# esp-mqtt-doorbell-receiver.net
KiCad netlist of a schematic drawn in EAGLE
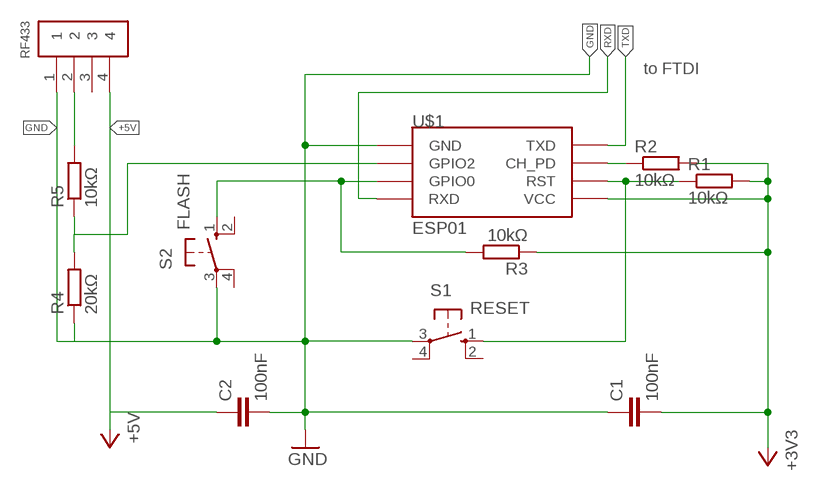
[diagram p0: schematic, sheet 1]

(export (version "E")
  (design (tool "Eeschema 10.0.6"))
  (components
    (comp (ref "C1")
      (value "100nF")
      (footprint "eagle-import:C025-025X050")
      (libsource (lib "eagle-import") (part "C-EU025-025X050"))
    )
    (comp (ref "C2")
      (value "100nF")
      (footprint "eagle-import:C025-025X050")
      (libsource (lib "eagle-import") (part "C-EU025-025X050"))
    )
    (comp (ref "R1")
      (value "10kΩ")
      (footprint "eagle-import:0204_7")
      (libsource (lib "eagle-import") (part "R-EU_0204/7"))
    )
    (comp (ref "R2")
      (value "10kΩ")
      (footprint "eagle-import:0204_7")
      (libsource (lib "eagle-import") (part "R-EU_0204/7"))
    )
    (comp (ref "R3")
      (value "10kΩ")
      (footprint "eagle-import:0204_7")
      (libsource (lib "eagle-import") (part "R-EU_0204/7"))
    )
    (comp (ref "R4")
      (value "20kΩ")
      (footprint "eagle-import:0204_7")
      (libsource (lib "eagle-import") (part "R-EU_0204/7"))
    )
    (comp (ref "R5")
      (value "10kΩ")
      (footprint "eagle-import:0204_7")
      (libsource (lib "eagle-import") (part "R-EU_0204/7"))
    )
    (comp (ref "RF433")
      (value "1X4-BIG")
      (footprint "eagle-import:1X04-BIG")
      (libsource (lib "eagle-import") (part "1X4-BIG"))
    )
    (comp (ref "S1")
      (value "RESET")
      (footprint "eagle-import:B3F-10XX")
      (fields (field (name "MPN") "B3F-1000"))
      (libsource (lib "eagle-import") (part "10-XX"))
    )
    (comp (ref "S2")
      (value "FLASH")
      (footprint "eagle-import:B3F-10XX")
      (fields (field (name "MPN") "B3F-1000"))
      (libsource (lib "eagle-import") (part "10-XX"))
    )
    (comp (ref "U$1")
      (value "ESP01")
      (footprint "eagle-import:ESP01")
      (libsource (lib "eagle-import") (part "ESP01"))
    )
  )
  (nets
    (net (code "1") (name "+3V3") (class "Default")
      (node (ref "C1") (pin "2") (pinfunction "2_2") (pintype "passive"))
      (node (ref "R1") (pin "2") (pinfunction "2_2") (pintype "passive"))
      (node (ref "R2") (pin "2") (pinfunction "2_2") (pintype "passive"))
      (node (ref "R3") (pin "1") (pinfunction "1_1") (pintype "passive"))
      (node (ref "U$1") (pin "VCC") (pinfunction "VCC_VCC") (pintype "bidirectional"))
    )
    (net (code "2") (name "+5V") (class "Default")
      (node (ref "C2") (pin "1") (pinfunction "1_1") (pintype "passive"))
      (node (ref "RF433") (pin "4") (pinfunction "4_4") (pintype "bidirectional"))
    )
    (net (code "3") (name "GND") (class "Default")
      (node (ref "C1") (pin "1") (pinfunction "1_1") (pintype "passive"))
      (node (ref "C2") (pin "2") (pinfunction "2_2") (pintype "passive"))
      (node (ref "R4") (pin "1") (pinfunction "1_1") (pintype "passive"))
      (node (ref "RF433") (pin "1") (pinfunction "1_1") (pintype "bidirectional"))
      (node (ref "S1") (pin "3") (pinfunction "P_3") (pintype "passive"))
      (node (ref "S2") (pin "3") (pinfunction "P_3") (pintype "passive"))
      (node (ref "U$1") (pin "GND") (pinfunction "GND_GND") (pintype "bidirectional"))
    )
    (net (code "4") (name "Net-(R2-Pad1)") (class "Default")
      (node (ref "R2") (pin "1") (pinfunction "1_1") (pintype "passive"))
      (node (ref "U$1") (pin "CH_PD") (pinfunction "CH_PD_CH_PD") (pintype "bidirectional"))
    )
    (net (code "5") (name "Net-(R4-Pad2)") (class "Default")
      (node (ref "R4") (pin "2") (pinfunction "2_2") (pintype "passive"))
      (node (ref "R5") (pin "1") (pinfunction "1_1") (pintype "passive"))
      (node (ref "U$1") (pin "GPIO2") (pinfunction "GPIO2_GPIO2") (pintype "bidirectional"))
    )
    (net (code "6") (name "Net-(R5-Pad2)") (class "Default")
      (node (ref "R5") (pin "2") (pinfunction "2_2") (pintype "passive"))
      (node (ref "RF433") (pin "2") (pinfunction "2_2") (pintype "bidirectional"))
    )
    (net (code "7") (name "Net-(S1-S)") (class "Default")
      (node (ref "R1") (pin "1") (pinfunction "1_1") (pintype "passive"))
      (node (ref "S1") (pin "1") (pinfunction "S_1") (pintype "passive"))
      (node (ref "U$1") (pin "RST") (pinfunction "RST_RST") (pintype "bidirectional"))
    )
    (net (code "8") (name "Net-(S2-S)") (class "Default")
      (node (ref "R3") (pin "2") (pinfunction "2_2") (pintype "passive"))
      (node (ref "S2") (pin "1") (pinfunction "S_1") (pintype "passive"))
      (node (ref "U$1") (pin "GPIO0") (pinfunction "GPIO0_GPIO0") (pintype "bidirectional"))
    )
    (net (code "9") (name "RXD") (class "Default")
      (node (ref "U$1") (pin "RX") (pinfunction "RXD_RX") (pintype "bidirectional"))
    )
    (net (code "10") (name "TXD") (class "Default")
      (node (ref "U$1") (pin "TX") (pinfunction "TXD_TX") (pintype "bidirectional"))
    )
    (net (code "11") (name "unconnected-(RF433-Pad3)") (class "Default")
      (node (ref "RF433") (pin "3") (pinfunction "3_3") (pintype "bidirectional"))
    )
    (net (code "12") (name "unconnected-(S1-P1-Pad4)") (class "Default")
      (node (ref "S1") (pin "4") (pinfunction "P1_4") (pintype "passive"))
    )
    (net (code "13") (name "unconnected-(S1-S1-Pad2)") (class "Default")
      (node (ref "S1") (pin "2") (pinfunction "S1_2") (pintype "passive"))
    )
    (net (code "14") (name "unconnected-(S2-P1-Pad4)") (class "Default")
      (node (ref "S2") (pin "4") (pinfunction "P1_4") (pintype "passive"))
    )
    (net (code "15") (name "unconnected-(S2-S1-Pad2)") (class "Default")
      (node (ref "S2") (pin "2") (pinfunction "S1_2") (pintype "passive"))
    )
  )
)
